# Switch2.net
KiCad netlist of a schematic drawn in Altium Designer
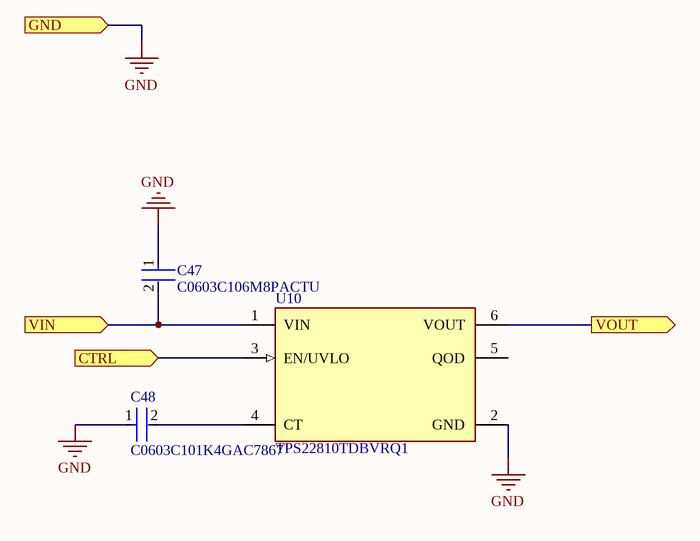
[diagram p0: Switch2.SchDoc]

(export (version "E")
  (design (tool "Eeschema 10.0.6"))
  (components
    (comp (ref "C47")
      (value "C0603C106M8PACTU")
      (footprint "FP-C0603C106M8PACTU-MFG")
      (description "CAP CER 10UF 10V X5R 0603")
      (libsource (lib "Altium Content Vault") (part "02cd4be3c70576c341d710602a673aa"))
    )
    (comp (ref "C48")
      (value "C0603C101K4GAC7867")
      (footprint "FP-C0603C-CF-MFG")
      (description "CAP CER 100PF 16V NP0 0603")
      (fields (field (name "MANUFACTURER") "KEMET") (field (name "TOLERANCE") "0.1"))
      (libsource (lib "Altium Content Vault") (part "b4654b650e69147ec39a6b967a45e02"))
    )
    (comp (ref "U10")
      (value "TPS22810TDBVRQ1")
      (footprint "FP-DBV0006A-MFG")
      (description "IC PWR SWITCH N-CHAN 1:1 SOT23-6")
      (libsource (lib "Altium Content Vault") (part "2d4a2501f31e6718a49a06b44f8b6c7"))
    )
  )
  (nets
    (net (code "1") (name "/CTRL") (class "Default")
      (node (ref "U10") (pin "3") (pinfunction "EN/UVLO_3") (pintype "input"))
    )
    (net (code "2") (name "/VIN") (class "Default")
      (node (ref "C47") (pin "2") (pinfunction "2_2") (pintype "passive"))
      (node (ref "U10") (pin "1") (pinfunction "VIN_1") (pintype "power_in"))
    )
    (net (code "3") (name "/VOUT") (class "Default")
      (node (ref "U10") (pin "6") (pinfunction "VOUT_6") (pintype "passive"))
    )
    (net (code "4") (name "GND") (class "Default")
      (node (ref "C47") (pin "1") (pinfunction "1_1") (pintype "passive"))
      (node (ref "C48") (pin "1") (pinfunction "1_1") (pintype "passive"))
      (node (ref "U10") (pin "2") (pinfunction "GND_2") (pintype "power_in"))
    )
    (net (code "5") (name "Net-(U10-CT)") (class "Default")
      (node (ref "C48") (pin "2") (pinfunction "2_2") (pintype "passive"))
      (node (ref "U10") (pin "4") (pinfunction "CT_4") (pintype "passive"))
    )
    (net (code "6") (name "unconnected-(U10-QOD-Pad5)") (class "Default")
      (node (ref "U10") (pin "5") (pinfunction "QOD_5") (pintype "passive"))
    )
  )
)
